# ECU_AutoRC_UC0_r00.net
KiCad netlist of a schematic drawn in Altium Designer
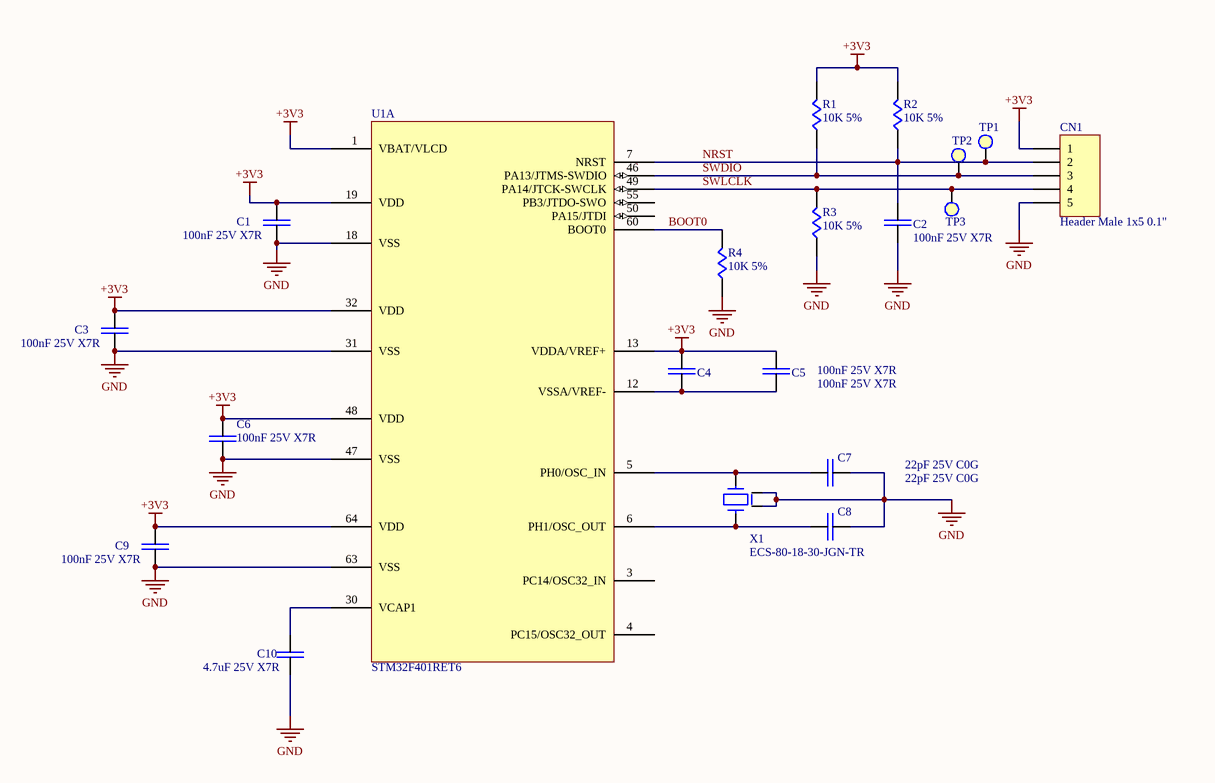
[diagram p0: ECU_AutoRC_UC0_r00.SchDoc]

(export (version "E")
  (design (tool "Eeschema 10.0.6"))
  (components
    (comp (ref "C1")
      (value "100nF 25V X7R")
      (footprint "C_0805")
      (description "Non Polarizated Capacitor")
      (libsource (lib "ECU_AutoRC_r00") (part "Capacitor NP"))
    )
    (comp (ref "C2")
      (value "100nF 25V X7R")
      (footprint "C_0805")
      (description "Non Polarizated Capacitor")
      (libsource (lib "ECU_AutoRC_r00") (part "Capacitor NP"))
    )
    (comp (ref "C3")
      (value "100nF 25V X7R")
      (footprint "C_0805")
      (description "Non Polarizated Capacitor")
      (libsource (lib "ECU_AutoRC_r00") (part "Capacitor NP"))
    )
    (comp (ref "C4")
      (value "100nF 25V X7R")
      (footprint "C_0805")
      (description "Non Polarizated Capacitor")
      (libsource (lib "ECU_AutoRC_r00") (part "Capacitor NP"))
    )
    (comp (ref "C5")
      (value "100nF 25V X7R")
      (footprint "C_0805")
      (description "Non Polarizated Capacitor")
      (libsource (lib "ECU_AutoRC_r00") (part "Capacitor NP"))
    )
    (comp (ref "C6")
      (value "100nF 25V X7R")
      (footprint "C_0805")
      (description "Non Polarizated Capacitor")
      (libsource (lib "ECU_AutoRC_r00") (part "Capacitor NP"))
    )
    (comp (ref "C7")
      (value "22pF 25V C0G")
      (footprint "C_0805")
      (description "Non Polarizated Capacitor")
      (libsource (lib "ECU_AutoRC_r00") (part "Capacitor NP"))
    )
    (comp (ref "C8")
      (value "22pF 25V C0G")
      (footprint "C_0805")
      (description "Non Polarizated Capacitor")
      (libsource (lib "ECU_AutoRC_r00") (part "Capacitor NP"))
    )
    (comp (ref "C9")
      (value "100nF 25V X7R")
      (footprint "C_0805")
      (description "Non Polarizated Capacitor")
      (libsource (lib "ECU_AutoRC_r00") (part "Capacitor NP"))
    )
    (comp (ref "C10")
      (value "4.7uF 25V X7R")
      (footprint "C_0805")
      (description "Non Polarizated Capacitor")
      (libsource (lib "ECU_AutoRC_r00") (part "Capacitor NP"))
    )
    (comp (ref "CN1")
      (value "Header Male 1x5 0.1\"")
      (footprint "Header_M_1x5_2mm")
      (description "Connector Generic 5 Vias")
      (libsource (lib "ECU_AutoRC_r00") (part "CONN_05P"))
    )
    (comp (ref "R1")
      (value "10K 5%")
      (footprint "R_0805")
      (description "Resistor")
      (libsource (lib "ECU_AutoRC_r00") (part "Resistor"))
    )
    (comp (ref "R2")
      (value "10K 5%")
      (footprint "R_0805")
      (description "Resistor")
      (libsource (lib "ECU_AutoRC_r00") (part "Resistor"))
    )
    (comp (ref "R3")
      (value "10K 5%")
      (footprint "R_0805")
      (description "Resistor")
      (libsource (lib "ECU_AutoRC_r00") (part "Resistor"))
    )
    (comp (ref "R4")
      (value "10K 5%")
      (footprint "R_0805")
      (description "Resistor")
      (libsource (lib "ECU_AutoRC_r00") (part "Resistor"))
    )
    (comp (ref "TP1")
      (value "Test Point")
      (footprint "TEST_POINT")
      (libsource (lib "ECU_AutoRC_r00") (part "TestPoint"))
    )
    (comp (ref "TP2")
      (value "Test Point")
      (footprint "TEST_POINT")
      (libsource (lib "ECU_AutoRC_r00") (part "TestPoint"))
    )
    (comp (ref "TP3")
      (value "Test Point")
      (footprint "TEST_POINT")
      (libsource (lib "ECU_AutoRC_r00") (part "TestPoint"))
    )
    (comp (ref "U1")
      (value "STM32F401RET6")
      (footprint "STM32F401T6")
      (description "STM32 Microcontroller")
      (libsource (lib "ECU_AutoRC_r00") (part "STM32F401RE"))
    )
    (comp (ref "X1")
      (value "ECS-80-18-30-JGN-TR")
      (footprint "XTAL_4N_ECS-80-10")
      (description "Xtal 4 Ports")
      (libsource (lib "ECU_AutoRC_r00") (part "CRYSTAL_4P"))
    )
  )
  (nets
    (net (code "1") (name "+3V3") (class "Default")
      (node (ref "C1") (pin "2") (pinfunction "2_2") (pintype "passive"))
      (node (ref "C3") (pin "2") (pinfunction "2_2") (pintype "passive"))
      (node (ref "C4") (pin "1") (pinfunction "1_1") (pintype "passive"))
      (node (ref "C5") (pin "1") (pinfunction "1_1") (pintype "passive"))
      (node (ref "C6") (pin "2") (pinfunction "2_2") (pintype "passive"))
      (node (ref "C9") (pin "2") (pinfunction "2_2") (pintype "passive"))
      (node (ref "CN1") (pin "1") (pinfunction "1_1") (pintype "passive"))
      (node (ref "R1") (pin "2") (pinfunction "2_2") (pintype "passive"))
      (node (ref "R2") (pin "2") (pinfunction "2_2") (pintype "passive"))
      (node (ref "U1") (pin "1") (pinfunction "VBAT/VLCD_1") (pintype "passive"))
      (node (ref "U1") (pin "13") (pinfunction "VDDA/VREF+_13") (pintype "passive"))
      (node (ref "U1") (pin "19") (pinfunction "VDD_19") (pintype "passive"))
      (node (ref "U1") (pin "32") (pinfunction "VDD_32") (pintype "passive"))
      (node (ref "U1") (pin "48") (pinfunction "VDD_48") (pintype "passive"))
      (node (ref "U1") (pin "64") (pinfunction "VDD_64") (pintype "passive"))
    )
    (net (code "2") (name "/BOOT0") (class "Default")
      (node (ref "R4") (pin "2") (pinfunction "2_2") (pintype "passive"))
      (node (ref "U1") (pin "60") (pinfunction "BOOT0_60") (pintype "passive"))
    )
    (net (code "3") (name "/NRST") (class "Default")
      (node (ref "C2") (pin "1") (pinfunction "1_1") (pintype "passive"))
      (node (ref "CN1") (pin "2") (pinfunction "2_2") (pintype "passive"))
      (node (ref "R2") (pin "1") (pinfunction "1_1") (pintype "passive"))
      (node (ref "TP1") (pin "1") (pintype "passive"))
      (node (ref "U1") (pin "7") (pinfunction "NRST_7") (pintype "passive"))
    )
    (net (code "4") (name "/SWDIO") (class "Default")
      (node (ref "CN1") (pin "3") (pinfunction "3_3") (pintype "passive"))
      (node (ref "R1") (pin "1") (pinfunction "1_1") (pintype "passive"))
      (node (ref "TP2") (pin "1") (pintype "passive"))
      (node (ref "U1") (pin "46") (pinfunction "PA13/JTMS-SWDIO_46") (pintype "bidirectional"))
    )
    (net (code "5") (name "/SWLCLK") (class "Default")
      (node (ref "CN1") (pin "4") (pinfunction "4_4") (pintype "passive"))
      (node (ref "R3") (pin "2") (pinfunction "2_2") (pintype "passive"))
      (node (ref "TP3") (pin "1") (pintype "passive"))
      (node (ref "U1") (pin "49") (pinfunction "PA14/JTCK-SWCLK_49") (pintype "bidirectional"))
    )
    (net (code "6") (name "GND") (class "Default")
      (node (ref "C1") (pin "1") (pinfunction "1_1") (pintype "passive"))
      (node (ref "C10") (pin "1") (pinfunction "1_1") (pintype "passive"))
      (node (ref "C2") (pin "2") (pinfunction "2_2") (pintype "passive"))
      (node (ref "C3") (pin "1") (pinfunction "1_1") (pintype "passive"))
      (node (ref "C6") (pin "1") (pinfunction "1_1") (pintype "passive"))
      (node (ref "C7") (pin "2") (pinfunction "2_2") (pintype "passive"))
      (node (ref "C8") (pin "2") (pinfunction "2_2") (pintype "passive"))
      (node (ref "C9") (pin "1") (pinfunction "1_1") (pintype "passive"))
      (node (ref "CN1") (pin "5") (pinfunction "5_5") (pintype "passive"))
      (node (ref "R3") (pin "1") (pinfunction "1_1") (pintype "passive"))
      (node (ref "R4") (pin "1") (pinfunction "1_1") (pintype "passive"))
      (node (ref "U1") (pin "18") (pinfunction "VSS_18") (pintype "passive"))
      (node (ref "U1") (pin "31") (pinfunction "VSS_31") (pintype "passive"))
      (node (ref "U1") (pin "47") (pinfunction "VSS_47") (pintype "passive"))
      (node (ref "U1") (pin "63") (pinfunction "VSS_63") (pintype "passive"))
      (node (ref "X1") (pin "2") (pinfunction "2_2") (pintype "passive"))
      (node (ref "X1") (pin "4") (pinfunction "4_4") (pintype "passive"))
    )
    (net (code "7") (name "Net-(U1A-PH0{slash}OSC_IN)") (class "Default")
      (node (ref "C7") (pin "1") (pinfunction "1_1") (pintype "passive"))
      (node (ref "U1") (pin "5") (pinfunction "PH0/OSC_IN_5") (pintype "passive"))
      (node (ref "X1") (pin "1") (pinfunction "1_1") (pintype "passive"))
    )
    (net (code "8") (name "Net-(U1A-PH1{slash}OSC_OUT)") (class "Default")
      (node (ref "C8") (pin "1") (pinfunction "1_1") (pintype "passive"))
      (node (ref "U1") (pin "6") (pinfunction "PH1/OSC_OUT_6") (pintype "passive"))
      (node (ref "X1") (pin "3") (pinfunction "3_3") (pintype "passive"))
    )
    (net (code "9") (name "Net-(U1A-VCAP1)") (class "Default")
      (node (ref "C10") (pin "2") (pinfunction "2_2") (pintype "passive"))
      (node (ref "U1") (pin "30") (pinfunction "VCAP1_30") (pintype "passive"))
    )
    (net (code "10") (name "Net-(U1A-VSSA{slash}VREF-)") (class "Default")
      (node (ref "C4") (pin "2") (pinfunction "2_2") (pintype "passive"))
      (node (ref "C5") (pin "2") (pinfunction "2_2") (pintype "passive"))
      (node (ref "U1") (pin "12") (pinfunction "VSSA/VREF-_12") (pintype "passive"))
    )
    (net (code "11") (name "unconnected-(U1A-PA15{slash}JTDI-Pad50)") (class "Default")
      (node (ref "U1") (pin "50") (pinfunction "PA15/JTDI_50") (pintype "bidirectional"))
    )
    (net (code "12") (name "unconnected-(U1A-PB3{slash}JTDO-SWO-Pad55)") (class "Default")
      (node (ref "U1") (pin "55") (pinfunction "PB3/JTDO-SWO_55") (pintype "bidirectional"))
    )
    (net (code "13") (name "unconnected-(U1A-PC14{slash}OSC32_IN-Pad3)") (class "Default")
      (node (ref "U1") (pin "3") (pinfunction "PC14/OSC32_IN_3") (pintype "passive"))
    )
    (net (code "14") (name "unconnected-(U1A-PC15{slash}OSC32_OUT-Pad4)") (class "Default")
      (node (ref "U1") (pin "4") (pinfunction "PC15/OSC32_OUT_4") (pintype "passive"))
    )
  )
)
